# Schematic.net
KiCad netlist of a schematic drawn in EAGLE
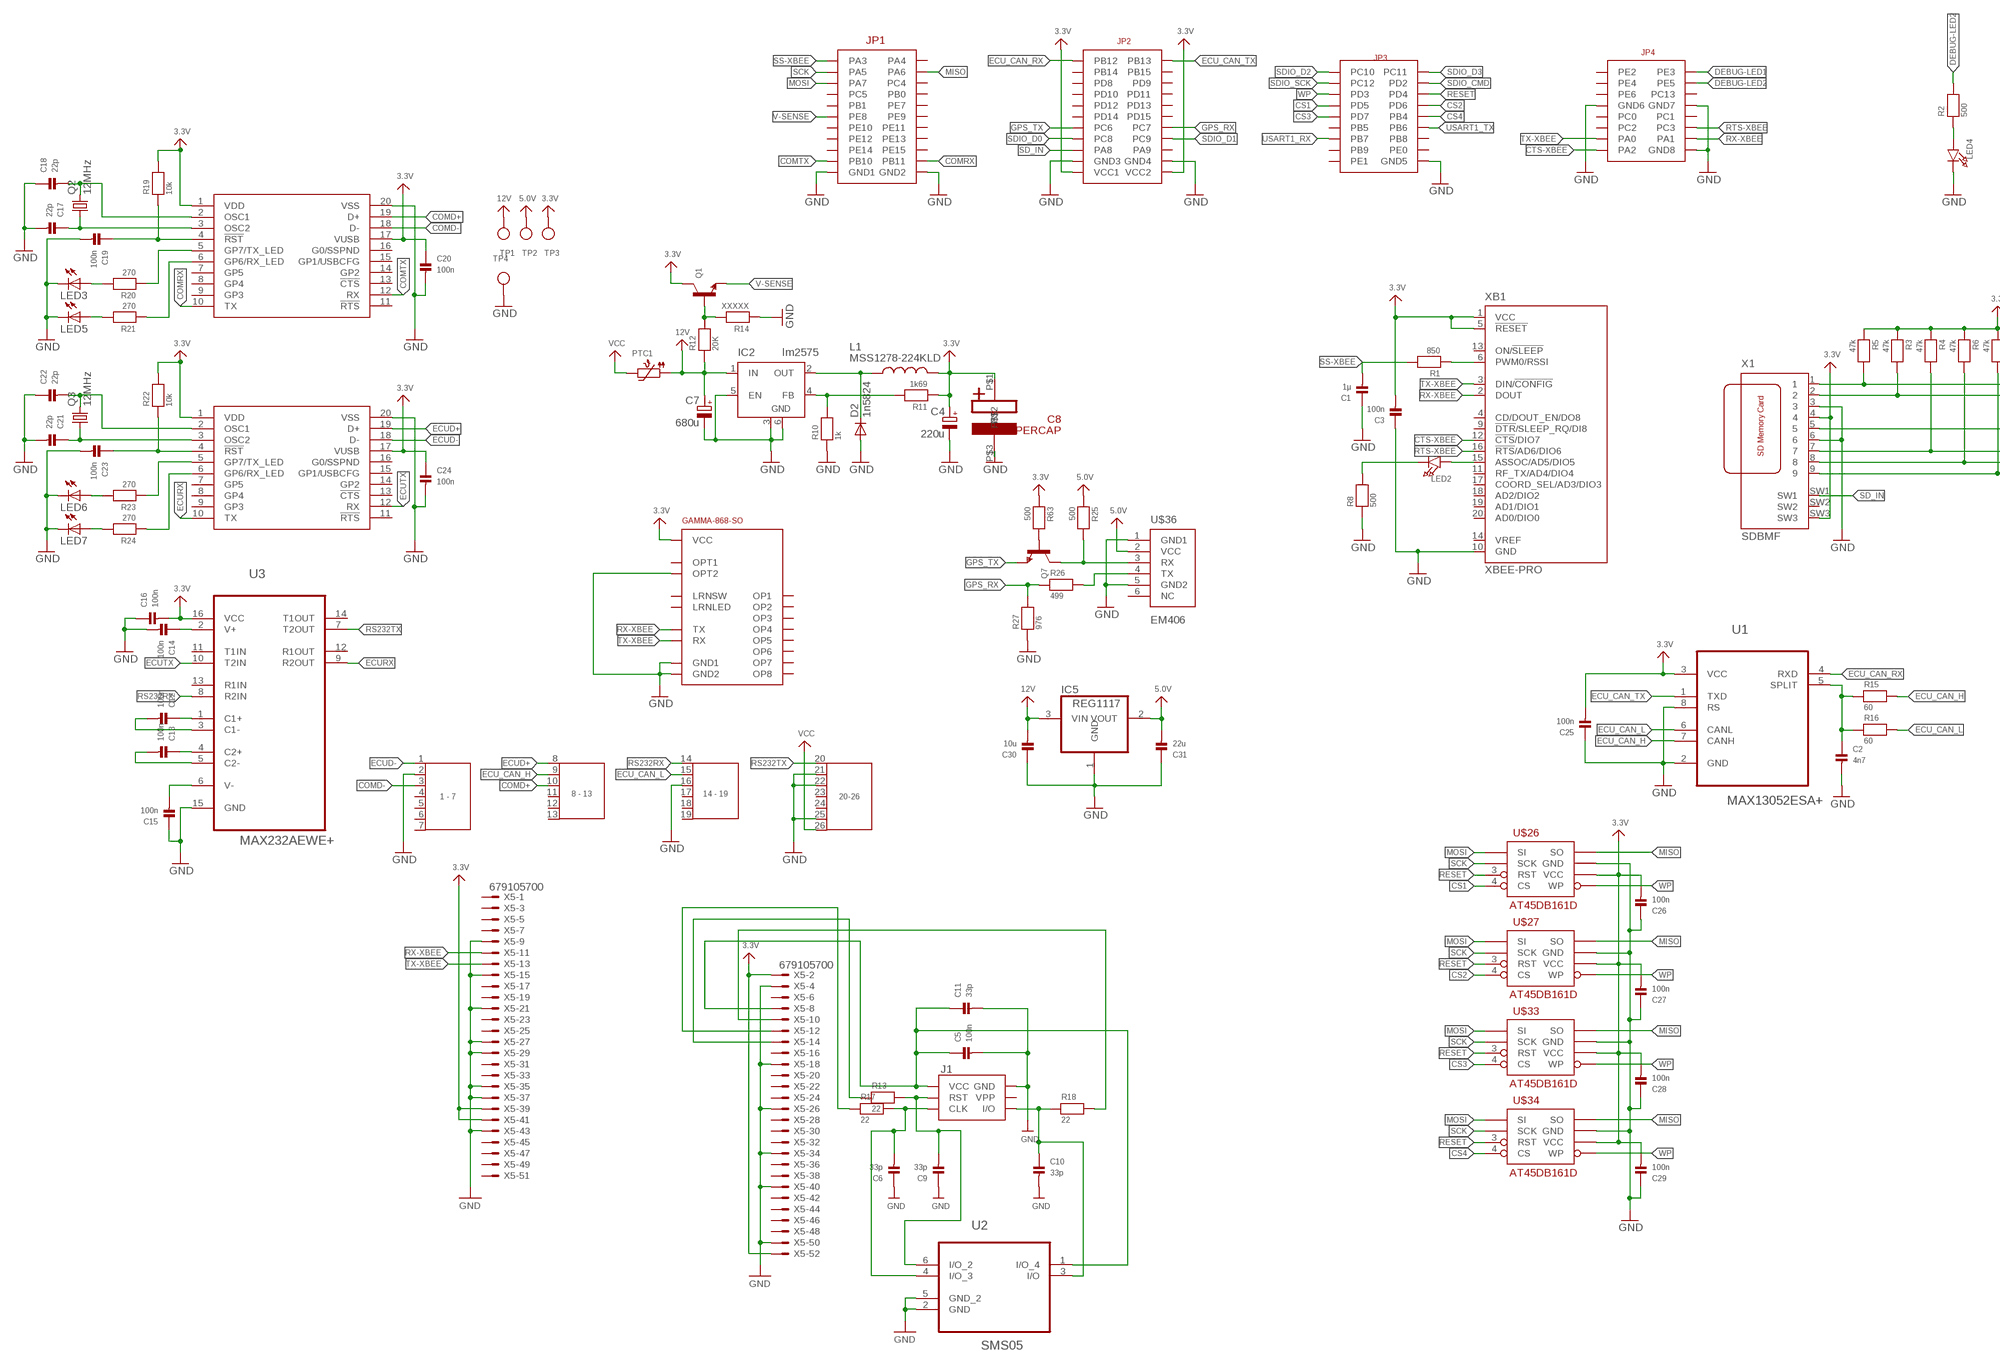
[diagram p0: schematic, sheet 1, part 1 of 2]
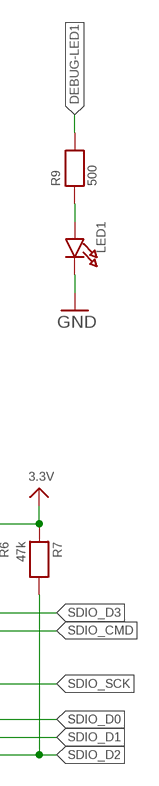
[diagram p1: schematic, sheet 1, part 2 of 2]

(export (version "E")
  (design (tool "Eeschema 10.0.6"))
  (components
    (comp (ref "C1")
      (value "1µ")
      (footprint "eagle-import:_0805")
      (libsource (lib "eagle-import") (part "CAP_CERAMIC_0805"))
    )
    (comp (ref "C2")
      (value "4n7")
      (footprint "eagle-import:0603")
      (libsource (lib "eagle-import") (part "CAP_CERAMIC0603"))
    )
    (comp (ref "C3")
      (value "100n")
      (footprint "eagle-import:_0603")
      (libsource (lib "eagle-import") (part "CAP_CERAMIC_0603"))
    )
    (comp (ref "C4")
      (value "220u")
      (footprint "eagle-import:E3,5-8")
      (libsource (lib "eagle-import") (part "CPOL-EUE3.5-8"))
    )
    (comp (ref "C5")
      (value "100n")
      (footprint "eagle-import:_0603")
      (libsource (lib "eagle-import") (part "CAP_CERAMIC_0603"))
    )
    (comp (ref "C6")
      (value "33p")
      (footprint "eagle-import:_0603")
      (libsource (lib "eagle-import") (part "CAP_CERAMIC_0603"))
    )
    (comp (ref "C7")
      (value "680u")
      (footprint "eagle-import:E5-10,5")
      (libsource (lib "eagle-import") (part "CPOL-EUE5-10.5"))
    )
    (comp (ref "C8")
      (value "SUPERCAP")
      (footprint "eagle-import:SUPERCAP")
      (libsource (lib "eagle-import") (part "SUPERCAP"))
    )
    (comp (ref "C9")
      (value "33p")
      (footprint "eagle-import:_0603")
      (libsource (lib "eagle-import") (part "CAP_CERAMIC_0603"))
    )
    (comp (ref "C10")
      (value "33p")
      (footprint "eagle-import:_0603")
      (libsource (lib "eagle-import") (part "CAP_CERAMIC_0603"))
    )
    (comp (ref "C11")
      (value "33p")
      (footprint "eagle-import:_0603")
      (libsource (lib "eagle-import") (part "CAP_CERAMIC_0603"))
    )
    (comp (ref "C12")
      (value "100n")
      (footprint "eagle-import:_0603")
      (libsource (lib "eagle-import") (part "CAP_CERAMIC_0603"))
    )
    (comp (ref "C13")
      (value "100n")
      (footprint "eagle-import:_0603")
      (libsource (lib "eagle-import") (part "CAP_CERAMIC_0603"))
    )
    (comp (ref "C14")
      (value "100n")
      (footprint "eagle-import:_0603")
      (libsource (lib "eagle-import") (part "CAP_CERAMIC_0603"))
    )
    (comp (ref "C15")
      (value "100n")
      (footprint "eagle-import:_0603")
      (libsource (lib "eagle-import") (part "CAP_CERAMIC_0603"))
    )
    (comp (ref "C16")
      (value "100n")
      (footprint "eagle-import:_0603")
      (libsource (lib "eagle-import") (part "CAP_CERAMIC_0603"))
    )
    (comp (ref "C17")
      (value "22p")
      (footprint "eagle-import:_0603")
      (libsource (lib "eagle-import") (part "CAP_CERAMIC_0603"))
    )
    (comp (ref "C18")
      (value "22p")
      (footprint "eagle-import:_0603")
      (libsource (lib "eagle-import") (part "CAP_CERAMIC_0603"))
    )
    (comp (ref "C19")
      (value "100n")
      (footprint "eagle-import:_0603")
      (libsource (lib "eagle-import") (part "CAP_CERAMIC_0603"))
    )
    (comp (ref "C20")
      (value "100n")
      (footprint "eagle-import:_0603")
      (libsource (lib "eagle-import") (part "CAP_CERAMIC_0603"))
    )
    (comp (ref "C21")
      (value "22p")
      (footprint "eagle-import:_0603")
      (libsource (lib "eagle-import") (part "CAP_CERAMIC_0603"))
    )
    (comp (ref "C22")
      (value "22p")
      (footprint "eagle-import:_0603")
      (libsource (lib "eagle-import") (part "CAP_CERAMIC_0603"))
    )
    (comp (ref "C23")
      (value "100n")
      (footprint "eagle-import:_0603")
      (libsource (lib "eagle-import") (part "CAP_CERAMIC_0603"))
    )
    (comp (ref "C24")
      (value "100n")
      (footprint "eagle-import:_0603")
      (libsource (lib "eagle-import") (part "CAP_CERAMIC_0603"))
    )
    (comp (ref "C25")
      (value "100n")
      (footprint "eagle-import:_0603")
      (libsource (lib "eagle-import") (part "CAP_CERAMIC_0603"))
    )
    (comp (ref "C26")
      (value "100n")
      (footprint "eagle-import:_0603")
      (libsource (lib "eagle-import") (part "CAP_CERAMIC_0603"))
    )
    (comp (ref "C27")
      (value "100n")
      (footprint "eagle-import:_0603")
      (libsource (lib "eagle-import") (part "CAP_CERAMIC_0603"))
    )
    (comp (ref "C28")
      (value "100n")
      (footprint "eagle-import:_0603")
      (libsource (lib "eagle-import") (part "CAP_CERAMIC_0603"))
    )
    (comp (ref "C29")
      (value "100n")
      (footprint "eagle-import:_0603")
      (libsource (lib "eagle-import") (part "CAP_CERAMIC_0603"))
    )
    (comp (ref "C30")
      (value "10u")
      (footprint "eagle-import:_0805")
      (libsource (lib "eagle-import") (part "CAP_CERAMIC_0805"))
    )
    (comp (ref "C31")
      (value "22u")
      (footprint "eagle-import:_0805")
      (libsource (lib "eagle-import") (part "CAP_CERAMIC_0805"))
    )
    (comp (ref "D2")
      (value "1n5824")
      (footprint "eagle-import:DO201-15")
      (libsource (lib "eagle-import") (part "1N5400"))
    )
    (comp (ref "IC2")
      (value "lm2575")
      (footprint "eagle-import:TO263-5")
      (libsource (lib "eagle-import") (part "LM2596S"))
    )
    (comp (ref "IC5")
      (value "REG1117")
      (footprint "eagle-import:SOT223")
      (libsource (lib "eagle-import") (part "REG1117"))
    )
    (comp (ref "J1")
      (value "SIMHOLDERSIM")
      (footprint "eagle-import:SIMHOLDER")
      (libsource (lib "eagle-import") (part "SIMHOLDERSIM"))
    )
    (comp (ref "L1")
      (value "MSS1278-224KLD")
      (footprint "eagle-import:CDRH125")
      (libsource (lib "eagle-import") (part "INDUCTORPWR"))
    )
    (comp (ref "LED1")
      (value "LED1206")
      (footprint "eagle-import:CHIPLED_1206")
      (libsource (lib "eagle-import") (part "LED1206"))
    )
    (comp (ref "LED2")
      (value "LED1206")
      (footprint "eagle-import:CHIPLED_1206")
      (libsource (lib "eagle-import") (part "LED1206"))
    )
    (comp (ref "LED3")
      (value "LEDCHIPLED_0805")
      (footprint "eagle-import:CHIPLED_0805")
      (libsource (lib "eagle-import") (part "LEDCHIPLED_0805"))
    )
    (comp (ref "LED4")
      (value "LED1206")
      (footprint "eagle-import:CHIPLED_1206")
      (libsource (lib "eagle-import") (part "LED1206"))
    )
    (comp (ref "LED5")
      (value "LEDCHIPLED_0805")
      (footprint "eagle-import:CHIPLED_0805")
      (libsource (lib "eagle-import") (part "LEDCHIPLED_0805"))
    )
    (comp (ref "LED6")
      (value "LEDCHIPLED_0805")
      (footprint "eagle-import:CHIPLED_0805")
      (libsource (lib "eagle-import") (part "LEDCHIPLED_0805"))
    )
    (comp (ref "LED7")
      (value "LEDCHIPLED_0805")
      (footprint "eagle-import:CHIPLED_0805")
      (libsource (lib "eagle-import") (part "LEDCHIPLED_0805"))
    )
    (comp (ref "PTC1")
      (value "PTC1812")
      (footprint "eagle-import:PTC1812")
      (libsource (lib "eagle-import") (part "PTC1812"))
    )
    (comp (ref "Q1")
      (value "TRANSISTOR_NPNWIDE")
      (footprint "eagle-import:SOT23-WIDE")
      (libsource (lib "eagle-import") (part "TRANSISTOR_NPNWIDE"))
    )
    (comp (ref "Q2")
      (value "12MHz")
      (footprint "eagle-import:HC49_S")
      (libsource (lib "eagle-import") (part "CRYSTALHC49S"))
    )
    (comp (ref "Q3")
      (value "12MHz")
      (footprint "eagle-import:HC49_S")
      (libsource (lib "eagle-import") (part "CRYSTALHC49S"))
    )
    (comp (ref "Q7")
      (value "TRANSISTOR_NPNWIDE")
      (footprint "eagle-import:SOT23-WIDE")
      (libsource (lib "eagle-import") (part "TRANSISTOR_NPNWIDE"))
    )
    (comp (ref "R1")
      (value "850")
      (footprint "eagle-import:_0603")
      (libsource (lib "eagle-import") (part "RESISTOR_0603"))
    )
    (comp (ref "R2")
      (value "500")
      (footprint "eagle-import:_0603")
      (libsource (lib "eagle-import") (part "RESISTOR_0603"))
    )
    (comp (ref "R3")
      (value "47k")
      (footprint "eagle-import:_0603")
      (libsource (lib "eagle-import") (part "RESISTOR_0603"))
    )
    (comp (ref "R4")
      (value "47k")
      (footprint "eagle-import:_0603")
      (libsource (lib "eagle-import") (part "RESISTOR_0603"))
    )
    (comp (ref "R5")
      (value "47k")
      (footprint "eagle-import:_0603")
      (libsource (lib "eagle-import") (part "RESISTOR_0603"))
    )
    (comp (ref "R6")
      (value "47k")
      (footprint "eagle-import:_0603")
      (libsource (lib "eagle-import") (part "RESISTOR_0603"))
    )
    (comp (ref "R7")
      (value "47k")
      (footprint "eagle-import:_0603")
      (libsource (lib "eagle-import") (part "RESISTOR_0603"))
    )
    (comp (ref "R8")
      (value "500")
      (footprint "eagle-import:_0603")
      (libsource (lib "eagle-import") (part "RESISTOR_0603"))
    )
    (comp (ref "R9")
      (value "500")
      (footprint "eagle-import:_0603")
      (libsource (lib "eagle-import") (part "RESISTOR_0603"))
    )
    (comp (ref "R10")
      (value "1k")
      (footprint "eagle-import:_0603")
      (libsource (lib "eagle-import") (part "RESISTOR_0603"))
    )
    (comp (ref "R11")
      (value "1k69")
      (footprint "eagle-import:_0603")
      (libsource (lib "eagle-import") (part "RESISTOR_0603"))
    )
    (comp (ref "R12")
      (value "20K")
      (footprint "eagle-import:_0603")
      (libsource (lib "eagle-import") (part "RESISTOR_0603"))
    )
    (comp (ref "R13")
      (value "22")
      (footprint "eagle-import:_0603")
      (libsource (lib "eagle-import") (part "RESISTOR_0603"))
    )
    (comp (ref "R14")
      (value "XXXXX")
      (footprint "eagle-import:_0603")
      (libsource (lib "eagle-import") (part "RESISTOR_0603"))
    )
    (comp (ref "R15")
      (value "60")
      (footprint "eagle-import:_0603")
      (libsource (lib "eagle-import") (part "RESISTOR_0603"))
    )
    (comp (ref "R16")
      (value "60")
      (footprint "eagle-import:_0603")
      (libsource (lib "eagle-import") (part "RESISTOR_0603"))
    )
    (comp (ref "R17")
      (value "22")
      (footprint "eagle-import:_0603")
      (libsource (lib "eagle-import") (part "RESISTOR_0603"))
    )
    (comp (ref "R18")
      (value "22")
      (footprint "eagle-import:_0603")
      (libsource (lib "eagle-import") (part "RESISTOR_0603"))
    )
    (comp (ref "R19")
      (value "10k")
      (footprint "eagle-import:_0603")
      (libsource (lib "eagle-import") (part "RESISTOR_0603"))
    )
    (comp (ref "R20")
      (value "270")
      (footprint "eagle-import:_0603")
      (libsource (lib "eagle-import") (part "RESISTOR_0603"))
    )
    (comp (ref "R21")
      (value "270")
      (footprint "eagle-import:_0603")
      (libsource (lib "eagle-import") (part "RESISTOR_0603"))
    )
    (comp (ref "R22")
      (value "10k")
      (footprint "eagle-import:_0603")
      (libsource (lib "eagle-import") (part "RESISTOR_0603"))
    )
    (comp (ref "R23")
      (value "270")
      (footprint "eagle-import:_0603")
      (libsource (lib "eagle-import") (part "RESISTOR_0603"))
    )
    (comp (ref "R24")
      (value "270")
      (footprint "eagle-import:_0603")
      (libsource (lib "eagle-import") (part "RESISTOR_0603"))
    )
    (comp (ref "R25")
      (value "500")
      (footprint "eagle-import:_0603")
      (libsource (lib "eagle-import") (part "RESISTOR_0603"))
    )
    (comp (ref "R26")
      (value "499")
      (footprint "eagle-import:_0603")
      (libsource (lib "eagle-import") (part "RESISTOR_0603"))
    )
    (comp (ref "R27")
      (value "976")
      (footprint "eagle-import:_0603")
      (libsource (lib "eagle-import") (part "RESISTOR_0603"))
    )
    (comp (ref "R63")
      (value "500")
      (footprint "eagle-import:_0603")
      (libsource (lib "eagle-import") (part "RESISTOR_0603"))
    )
    (comp (ref "TP1")
      (value "TESTPOINT")
      (footprint "eagle-import:TESTPOINT_SMT")
      (libsource (lib "eagle-import") (part "TESTPOINT"))
    )
    (comp (ref "TP2")
      (value "TESTPOINT")
      (footprint "eagle-import:TESTPOINT_SMT")
      (libsource (lib "eagle-import") (part "TESTPOINT"))
    )
    (comp (ref "TP3")
      (value "TESTPOINT")
      (footprint "eagle-import:TESTPOINT_SMT")
      (libsource (lib "eagle-import") (part "TESTPOINT"))
    )
    (comp (ref "TP4")
      (value "TESTPOINT")
      (footprint "eagle-import:TESTPOINT_SMT")
      (libsource (lib "eagle-import") (part "TESTPOINT"))
    )
    (comp (ref "U$1")
      (value "CPU-BOARD")
      (footprint "eagle-import:CPU-BOARD-JP1")
      (libsource (lib "eagle-import") (part "CPU-BOARD"))
    )
    (comp (ref "U$18")
      (value "SUPERSEAL-26")
      (footprint "eagle-import:SUPERSEAL-26")
      (libsource (lib "eagle-import") (part "SUPERSEAL-26"))
    )
    (comp (ref "U$24")
      (value "MCP2200")
      (footprint "eagle-import:SO20L")
      (libsource (lib "eagle-import") (part "MCP2200"))
    )
    (comp (ref "U$26")
      (value "AT45DB161D")
      (footprint "eagle-import:SO08-EIAJ")
      (libsource (lib "eagle-import") (part "AT45DB161D"))
    )
    (comp (ref "U$27")
      (value "AT45DB161D")
      (footprint "eagle-import:SO08-EIAJ")
      (libsource (lib "eagle-import") (part "AT45DB161D"))
    )
    (comp (ref "U$29")
      (value "MCP2200")
      (footprint "eagle-import:SO20L")
      (libsource (lib "eagle-import") (part "MCP2200"))
    )
    (comp (ref "U$32")
      (value "GAMMA-868-SO")
      (footprint "eagle-import:UNICORN_V2_GAMMA-868-SO")
      (libsource (lib "eagle-import") (part "GAMMA-868-SO"))
    )
    (comp (ref "U$33")
      (value "AT45DB161D")
      (footprint "eagle-import:SO08-EIAJ")
      (libsource (lib "eagle-import") (part "AT45DB161D"))
    )
    (comp (ref "U$34")
      (value "AT45DB161D")
      (footprint "eagle-import:SO08-EIAJ")
      (libsource (lib "eagle-import") (part "AT45DB161D"))
    )
    (comp (ref "U$36")
      (value "EM406")
      (footprint "eagle-import:EM406")
      (libsource (lib "eagle-import") (part "EM406"))
    )
    (comp (ref "U1")
      (value "MAX13052ESA+")
      (footprint "eagle-import:SOIC127P600X175-8N")
      (fields
        (field (name "MPN") "MAX13052ESA+")
        (field (name "OC_FARNELL") "1600112")
        (field (name "OC_NEWARK") "99K2875")
        (field (name "PACKAGE") "SOIC-8")
        (field (name "SUPPLIER") "Maxim")
      )
      (libsource (lib "eagle-import") (part "MAX13052ESA+"))
    )
    (comp (ref "U2")
      (value "SMS05")
      (footprint "eagle-import:SOT95P280X145-6N")
      (libsource (lib "eagle-import") (part "SMS05"))
    )
    (comp (ref "U3")
      (value "MAX232AEWE+")
      (footprint "eagle-import:SOIC127P1032X265-16N")
      (libsource (lib "eagle-import") (part "MAX232AEWE+"))
    )
    (comp (ref "X1")
      (value "SDBMF")
      (footprint "eagle-import:SDBMF-009XXBXX2")
      (libsource (lib "eagle-import") (part "SDBMF"))
    )
    (comp (ref "X5")
      (value "679105700")
      (footprint "eagle-import:679105700")
      (fields (field (name "MPN") "67910-5700"))
      (libsource (lib "eagle-import") (part "679105700"))
    )
    (comp (ref "XB1")
      (value "XBEE-PRO")
      (footprint "eagle-import:XBEE-PRO")
      (fields (field (name "MPN") "XBP24-AWI-001"))
      (libsource (lib "eagle-import") (part "XBEE-PRO"))
    )
  )
  (nets
    (net (code "1") (name "3.3V") (class "Default")
      (node (ref "C16") (pin "2") (pinfunction "P$2_2") (pintype "passive"))
      (node (ref "C20") (pin "1") (pinfunction "P$1_1") (pintype "passive"))
      (node (ref "C24") (pin "1") (pinfunction "P$1_1") (pintype "passive"))
      (node (ref "C25") (pin "2") (pinfunction "P$2_2") (pintype "passive"))
      (node (ref "C26") (pin "2") (pinfunction "P$2_2") (pintype "passive"))
      (node (ref "C27") (pin "2") (pinfunction "P$2_2") (pintype "passive"))
      (node (ref "C28") (pin "2") (pinfunction "P$2_2") (pintype "passive"))
      (node (ref "C29") (pin "2") (pinfunction "P$2_2") (pintype "passive"))
      (node (ref "C3") (pin "2") (pinfunction "P$2_2") (pintype "passive"))
      (node (ref "C4") (pin "+") (pinfunction "+_+") (pintype "passive"))
      (node (ref "C8") (pin "P$1") (pinfunction "P$1_P$1") (pintype "bidirectional"))
      (node (ref "L1") (pin "2") (pinfunction "2_2") (pintype "passive"))
      (node (ref "Q1") (pin "3") (pinfunction "C_3") (pintype "passive"))
      (node (ref "R11") (pin "1") (pinfunction "1_1") (pintype "passive"))
      (node (ref "R19") (pin "2") (pinfunction "2_2") (pintype "passive"))
      (node (ref "R22") (pin "2") (pinfunction "2_2") (pintype "passive"))
      (node (ref "R3") (pin "1") (pinfunction "1_1") (pintype "passive"))
      (node (ref "R4") (pin "1") (pinfunction "1_1") (pintype "passive"))
      (node (ref "R5") (pin "1") (pinfunction "1_1") (pintype "passive"))
      (node (ref "R6") (pin "1") (pinfunction "1_1") (pintype "passive"))
      (node (ref "R63") (pin "1") (pinfunction "1_1") (pintype "passive"))
      (node (ref "R7") (pin "1") (pinfunction "1_1") (pintype "passive"))
      (node (ref "TP3") (pin "P$1") (pinfunction "P$1_P$1") (pintype "bidirectional"))
      (node (ref "U$1") (pin "P$43") (pinfunction "VCC1_P$43") (pintype "bidirectional"))
      (node (ref "U$1") (pin "P$44") (pinfunction "VCC2_P$44") (pintype "bidirectional"))
      (node (ref "U$24") (pin "1") (pinfunction "VDD_1") (pintype "bidirectional"))
      (node (ref "U$24") (pin "17") (pinfunction "VUSB_17") (pintype "bidirectional"))
      (node (ref "U$26") (pin "6") (pinfunction "VCC_6") (pintype "bidirectional"))
      (node (ref "U$27") (pin "6") (pinfunction "VCC_6") (pintype "bidirectional"))
      (node (ref "U$29") (pin "1") (pinfunction "VDD_1") (pintype "bidirectional"))
      (node (ref "U$29") (pin "17") (pinfunction "VUSB_17") (pintype "bidirectional"))
      (node (ref "U$32") (pin "P$16") (pinfunction "VCC_P$16") (pintype "bidirectional"))
      (node (ref "U$33") (pin "6") (pinfunction "VCC_6") (pintype "bidirectional"))
      (node (ref "U$34") (pin "6") (pinfunction "VCC_6") (pintype "bidirectional"))
      (node (ref "U1") (pin "3") (pinfunction "VCC_3") (pintype "power_in"))
      (node (ref "U3") (pin "16") (pinfunction "VCC_16") (pintype "power_in"))
      (node (ref "X1") (pin "4") (pinfunction "4_4") (pintype "passive"))
      (node (ref "X1") (pin "SW3") (pinfunction "SW3_SW3") (pintype "passive"))
      (node (ref "X5") (pin "2") (pinfunction "S_2") (pintype "passive"))
      (node (ref "X5") (pin "39") (pinfunction "S_39") (pintype "passive"))
      (node (ref "X5") (pin "41") (pinfunction "S_41") (pintype "passive"))
      (node (ref "X5") (pin "52") (pinfunction "S_52") (pintype "passive"))
      (node (ref "XB1") (pin "1") (pinfunction "VCC_1") (pintype "power_in"))
      (node (ref "XB1") (pin "5") (pinfunction "~{RESET}_5") (pintype "input"))
    )
    (net (code "2") (name "5.0V") (class "Default")
      (node (ref "C31") (pin "2") (pinfunction "P$2_2") (pintype "passive"))
      (node (ref "IC5") (pin "2") (pinfunction "VOUT_2") (pintype "output"))
      (node (ref "R25") (pin "1") (pinfunction "1_1") (pintype "passive"))
      (node (ref "TP2") (pin "P$1") (pinfunction "P$1_P$1") (pintype "bidirectional"))
      (node (ref "U$36") (pin "2") (pinfunction "VCC_2") (pintype "bidirectional"))
    )
    (net (code "3") (name "12V") (class "Default")
      (node (ref "C30") (pin "2") (pinfunction "P$2_2") (pintype "passive"))
      (node (ref "C7") (pin "+") (pinfunction "+_+") (pintype "passive"))
      (node (ref "IC2") (pin "1") (pinfunction "IN_1") (pintype "input"))
      (node (ref "IC5") (pin "3") (pinfunction "VIN_3") (pintype "input"))
      (node (ref "PTC1") (pin "P$1") (pinfunction "1_P$1") (pintype "passive"))
      (node (ref "R12") (pin "1") (pinfunction "1_1") (pintype "passive"))
      (node (ref "TP1") (pin "P$1") (pinfunction "P$1_P$1") (pintype "bidirectional"))
    )
    (net (code "4") (name "COMD+") (class "Default")
      (node (ref "U$18") (pin "10") (pinfunction "P$3_10") (pintype "bidirectional"))
      (node (ref "U$24") (pin "19") (pinfunction "D+_19") (pintype "bidirectional"))
    )
    (net (code "5") (name "COMD-") (class "Default")
      (node (ref "U$18") (pin "3") (pinfunction "P$3_3") (pintype "bidirectional"))
      (node (ref "U$24") (pin "18") (pinfunction "D-_18") (pintype "bidirectional"))
    )
    (net (code "6") (name "COMRX") (class "Default")
      (node (ref "U$1") (pin "P$22") (pinfunction "PB11_P$22") (pintype "bidirectional"))
      (node (ref "U$24") (pin "10") (pinfunction "TX_10") (pintype "bidirectional"))
    )
    (net (code "7") (name "COMTX") (class "Default")
      (node (ref "U$1") (pin "P$21") (pinfunction "PB10_P$21") (pintype "bidirectional"))
      (node (ref "U$24") (pin "12") (pinfunction "RX_12") (pintype "bidirectional"))
    )
    (net (code "8") (name "CS1") (class "Default")
      (node (ref "U$1") (pin "P$51") (pinfunction "PD5_P$51") (pintype "bidirectional"))
      (node (ref "U$26") (pin "4") (pinfunction "CS_4") (pintype "bidirectional"))
    )
    (net (code "9") (name "CS2") (class "Default")
      (node (ref "U$1") (pin "P$52") (pinfunction "PD6_P$52") (pintype "bidirectional"))
      (node (ref "U$27") (pin "4") (pinfunction "CS_4") (pintype "bidirectional"))
    )
    (net (code "10") (name "CS3") (class "Default")
      (node (ref "U$1") (pin "P$53") (pinfunction "PD7_P$53") (pintype "bidirectional"))
      (node (ref "U$33") (pin "4") (pinfunction "CS_4") (pintype "bidirectional"))
    )
    (net (code "11") (name "CS4") (class "Default")
      (node (ref "U$1") (pin "P$54") (pinfunction "PB4_P$54") (pintype "bidirectional"))
      (node (ref "U$34") (pin "4") (pinfunction "CS_4") (pintype "bidirectional"))
    )
    (net (code "12") (name "CTS-XBEE") (class "Default")
      (node (ref "U$1") (pin "P$77") (pinfunction "PA2_P$77") (pintype "bidirectional"))
      (node (ref "XB1") (pin "12") (pinfunction "~{CTS}/DIO7_12") (pintype "bidirectional"))
    )
    (net (code "13") (name "DEBUG-LED1") (class "Default")
      (node (ref "R9") (pin "2") (pinfunction "2_2") (pintype "passive"))
      (node (ref "U$1") (pin "P$64") (pinfunction "PE3_P$64") (pintype "bidirectional"))
    )
    (net (code "14") (name "DEBUG-LED2") (class "Default")
      (node (ref "R2") (pin "2") (pinfunction "2_2") (pintype "passive"))
      (node (ref "U$1") (pin "P$66") (pinfunction "PE5_P$66") (pintype "bidirectional"))
    )
    (net (code "15") (name "ECUD+") (class "Default")
      (node (ref "U$18") (pin "8") (pinfunction "P$1_8") (pintype "bidirectional"))
      (node (ref "U$29") (pin "19") (pinfunction "D+_19") (pintype "bidirectional"))
    )
    (net (code "16") (name "ECUD-") (class "Default")
      (node (ref "U$18") (pin "1") (pinfunction "P$1_1") (pintype "bidirectional"))
      (node (ref "U$29") (pin "18") (pinfunction "D-_18") (pintype "bidirectional"))
    )
    (net (code "17") (name "ECURX") (class "Default")
      (node (ref "U$29") (pin "10") (pinfunction "TX_10") (pintype "bidirectional"))
      (node (ref "U3") (pin "9") (pinfunction "R2OUT_9") (pintype "output"))
    )
    (net (code "18") (name "ECUTX") (class "Default")
      (node (ref "U$29") (pin "12") (pinfunction "RX_12") (pintype "bidirectional"))
      (node (ref "U3") (pin "10") (pinfunction "T2IN_10") (pintype "input"))
    )
    (net (code "19") (name "ECU_CAN_H") (class "Default")
      (node (ref "R15") (pin "2") (pinfunction "2_2") (pintype "passive"))
      (node (ref "U$18") (pin "9") (pinfunction "P$2_9") (pintype "bidirectional"))
      (node (ref "U1") (pin "7") (pinfunction "CANH_7") (pintype "input"))
    )
    (net (code "20") (name "ECU_CAN_L") (class "Default")
      (node (ref "R16") (pin "2") (pinfunction "2_2") (pintype "passive"))
      (node (ref "U$18") (pin "15") (pinfunction "P$2_15") (pintype "bidirectional"))
      (node (ref "U1") (pin "6") (pinfunction "CANL_6") (pintype "input"))
    )
    (net (code "21") (name "ECU_CAN_RX") (class "Default")
      (node (ref "U$1") (pin "P$23") (pinfunction "PB12_P$23") (pintype "bidirectional"))
      (node (ref "U1") (pin "4") (pinfunction "RXD_4") (pintype "output"))
    )
    (net (code "22") (name "ECU_CAN_TX") (class "Default")
      (node (ref "U$1") (pin "P$24") (pinfunction "PB13_P$24") (pintype "bidirectional"))
      (node (ref "U1") (pin "1") (pinfunction "TXD_1") (pintype "input"))
    )
    (net (code "23") (name "GND") (class "Default")
      (node (ref "C1") (pin "1") (pinfunction "P$1_1") (pintype "passive"))
      (node (ref "C10") (pin "2") (pinfunction "P$2_2") (pintype "passive"))
      (node (ref "C11") (pin "2") (pinfunction "P$2_2") (pintype "passive"))
      (node (ref "C14") (pin "2") (pinfunction "P$2_2") (pintype "passive"))
      (node (ref "C15") (pin "1") (pinfunction "P$1_1") (pintype "passive"))
      (node (ref "C16") (pin "1") (pinfunction "P$1_1") (pintype "passive"))
      (node (ref "C17") (pin "2") (pinfunction "P$2_2") (pintype "passive"))
      (node (ref "C18") (pin "1") (pinfunction "P$1_1") (pintype "passive"))
      (node (ref "C19") (pin "2") (pinfunction "P$2_2") (pintype "passive"))
      (node (ref "C2") (pin "2") (pinfunction "P$2_2") (pintype "passive"))
      (node (ref "C20") (pin "2") (pinfunction "P$2_2") (pintype "passive"))
      (node (ref "C21") (pin "2") (pinfunction "P$2_2") (pintype "passive"))
      (node (ref "C22") (pin "1") (pinfunction "P$1_1") (pintype "passive"))
      (node (ref "C23") (pin "2") (pinfunction "P$2_2") (pintype "passive"))
      (node (ref "C24") (pin "2") (pinfunction "P$2_2") (pintype "passive"))
      (node (ref "C25") (pin "1") (pinfunction "P$1_1") (pintype "passive"))
      (node (ref "C26") (pin "1") (pinfunction "P$1_1") (pintype "passive"))
      (node (ref "C27") (pin "1") (pinfunction "P$1_1") (pintype "passive"))
      (node (ref "C28") (pin "1") (pinfunction "P$1_1") (pintype "passive"))
      (node (ref "C29") (pin "1") (pinfunction "P$1_1") (pintype "passive"))
      (node (ref "C3") (pin "1") (pinfunction "P$1_1") (pintype "passive"))
      (node (ref "C30") (pin "1") (pinfunction "P$1_1") (pintype "passive"))
      (node (ref "C31") (pin "1") (pinfunction "P$1_1") (pintype "passive"))
      (node (ref "C4") (pin "-") (pinfunction "-_-") (pintype "passive"))
      (node (ref "C5") (pin "2") (pinfunction "P$2_2") (pintype "passive"))
      (node (ref "C6") (pin "1") (pinfunction "P$1_1") (pintype "passive"))
      (node (ref "C7") (pin "-") (pinfunction "-_-") (pintype "passive"))
      (node (ref "C8") (pin "P$3") (pinfunction "P$2_P$3") (pintype "bidirectional"))
      (node (ref "C9") (pin "1") (pinfunction "P$1_1") (pintype "passive"))
      (node (ref "D2") (pin "A") (pinfunction "A_A") (pintype "passive"))
      (node (ref "IC2") (pin "3") (pinfunction "GND_3") (pintype "power_in"))
      (node (ref "IC2") (pin "5") (pinfunction "EN_5") (pintype "input"))
      (node (ref "IC2") (pin "6") (pinfunction "GND_6") (pintype "power_in"))
      (node (ref "IC5") (pin "1") (pinfunction "GND_1") (pintype "power_in"))
      (node (ref "J1") (pin "C5") (pinfunction "GND_C5") (pintype "power_in"))
      (node (ref "LED1") (pin "C") (pinfunction "C_C") (pintype "passive"))
      (node (ref "LED3") (pin "C") (pinfunction "C_C") (pintype "passive"))
      (node (ref "LED4") (pin "C") (pinfunction "C_C") (pintype "passive"))
      (node (ref "LED5") (pin "C") (pinfunction "C_C") (pintype "passive"))
      (node (ref "LED6") (pin "C") (pinfunction "C_C") (pintype "passive"))
      (node (ref "LED7") (pin "C") (pinfunction "C_C") (pintype "passive"))
      (node (ref "R10") (pin "1") (pinfunction "1_1") (pintype "passive"))
      (node (ref "R14") (pin "1") (pinfunction "1_1") (pintype "passive"))
      (node (ref "R27") (pin "1") (pinfunction "1_1") (pintype "passive"))
      (node (ref "R8") (pin "1") (pinfunction "1_1") (pintype "passive"))
      (node (ref "TP4") (pin "P$1") (pinfunction "P$1_P$1") (pintype "bidirectional"))
      (node (ref "U$1") (pin "P$19") (pinfunction "GND1_P$19") (pintype "bidirectional"))
      (node (ref "U$1") (pin "P$20") (pinfunction "GND2_P$20") (pintype "bidirectional"))
      (node (ref "U$1") (pin "P$41") (pinfunction "GND3_P$41") (pintype "bidirectional"))
      (node (ref "U$1") (pin "P$42") (pinfunction "GND4_P$42") (pintype "bidirectional"))
      (node (ref "U$1") (pin "P$62") (pinfunction "GND5_P$62") (pintype "bidirectional"))
      (node (ref "U$1") (pin "P$69") (pinfunction "GND6_P$69") (pintype "bidirectional"))
      (node (ref "U$1") (pin "P$70") (pinfunction "GND7_P$70") (pintype "bidirectional"))
      (node (ref "U$1") (pin "P$78") (pinfunction "GND8_P$78") (pintype "bidirectional"))
      (node (ref "U$18") (pin "16") (pinfunction "P$3_16") (pintype "bidirectional"))
      (node (ref "U$18") (pin "2") (pinfunction "P$2_2") (pintype "bidirectional"))
      (node (ref "U$18") (pin "21") (pinfunction "P$2_21") (pintype "bidirectional"))
      (node (ref "U$18") (pin "22") (pinfunction "P$3_22") (pintype "bidirectional"))
      (node (ref "U$18") (pin "25") (pinfunction "P$6_25") (pintype "bidirectional"))
      (node (ref "U$24") (pin "20") (pinfunction "VSS_20") (pintype "bidirectional"))
      (node (ref "U$26") (pin "7") (pinfunction "GND_7") (pintype "bidirectional"))
      (node (ref "U$27") (pin "7") (pinfunction "GND_7") (pintype "bidirectional"))
      (node (ref "U$29") (pin "20") (pinfunction "VSS_20") (pintype "bidirectional"))
      (node (ref "U$32") (pin "P$14") (pinfunction "OPT2_P$14") (pintype "bidirectional"))
      (node (ref "U$32") (pin "P$15") (pinfunction "GND2_P$15") (pintype "bidirectional"))
      (node (ref "U$32") (pin "P$2") (pinfunction "GND1_P$2") (pintype "bidirectional"))
      (node (ref "U$33") (pin "7") (pinfunction "GND_7") (pintype "bidirectional"))
      (node (ref "U$34") (pin "7") (pinfunction "GND_7") (pintype "bidirectional"))
      (node (ref "U$36") (pin "1") (pinfunction "GND1_1") (pintype "bidirectional"))
      (node (ref "U$36") (pin "5") (pinfunction "GND2_5") (pintype "bidirectional"))
      (node (ref "U1") (pin "2") (pinfunction "GND_2") (pintype "passive"))
      (node (ref "U1") (pin "8") (pinfunction "RS_8") (pintype "input"))
      (node (ref "U2") (pin "2") (pinfunction "GND_2") (pintype "passive"))
      (node (ref "U2") (pin "5") (pinfunction "GND_2_5") (pintype "passive"))
      (node (ref "U3") (pin "15") (pinfunction "GND_15") (pintype "passive"))
      (node (ref "X1") (pin "3") (pinfunction "3_3") (pintype "passive"))
      (node (ref "X1") (pin "6") (pinfunction "6_6") (pintype "passive"))
      (node (ref "X5") (pin "15") (pinfunction "S_15") (pintype "passive"))
      (node (ref "X5") (pin "18") (pinfunction "S_18") (pintype "passive"))
      (node (ref "X5") (pin "21") (pinfunction "S_21") (pintype "passive"))
      (node (ref "X5") (pin "26") (pinfunction "S_26") (pintype "passive"))
      (node (ref "X5") (pin "27") (pinfunction "S_27") (pintype "passive"))
      (node (ref "X5") (pin "29") (pinfunction "S_29") (pintype "passive"))
      (node (ref "X5") (pin "34") (pinfunction "S_34") (pintype "passive"))
      (node (ref "X5") (pin "35") (pinfunction "S_35") (pintype "passive"))
      (node (ref "X5") (pin "37") (pinfunction "S_37") (pintype "passive"))
      (node (ref "X5") (pin "4") (pinfunction "S_4") (pintype "passive"))
      (node (ref "X5") (pin "40") (pinfunction "S_40") (pintype "passive"))
      (node (ref "X5") (pin "43") (pinfunction "S_43") (pintype "passive"))
      (node (ref "X5") (pin "50") (pinfunction "S_50") (pintype "passive"))
      (node (ref "X5") (pin "9") (pinfunction "S_9") (pintype "passive"))
      (node (ref "XB1") (pin "10") (pinfunction "GND_10") (pintype "power_in"))
    )
    (net (code "24") (name "GPS_RX") (class "Default")
      (node (ref "R26") (pin "1") (pinfunction "1_1") (pintype "passive"))
      (node (ref "R27") (pin "2") (pinfunction "2_2") (pintype "passive"))
      (node (ref "U$1") (pin "P$36") (pinfunction "PC7_P$36") (pintype "bidirectional"))
    )
    (net (code "25") (name "GPS_TX") (class "Default")
      (node (ref "Q7") (pin "2") (pinfunction "E_2") (pintype "passive"))
      (node (ref "U$1") (pin "P$35") (pinfunction "PC6_P$35") (pintype "bidirectional"))
    )
    (net (code "26") (name "MISO") (class "Default")
      (node (ref "U$1") (pin "P$4") (pinfunction "PA6_P$4") (pintype "bidirectional"))
      (node (ref "U$26") (pin "8") (pinfunction "SO_8") (pintype "bidirectional"))
      (node (ref "U$27") (pin "8") (pinfunction "SO_8") (pintype "bidirectional"))
      (node (ref "U$33") (pin "8") (pinfunction "SO_8") (pintype "bidirectional"))
      (node (ref "U$34") (pin "8") (pinfunction "SO_8") (pintype "bidirectional"))
    )
    (net (code "27") (name "MOSI") (class "Default")
      (node (ref "U$1") (pin "P$5") (pinfunction "PA7_P$5") (pintype "bidirectional"))
      (node (ref "U$26") (pin "1") (pinfunction "SI_1") (pintype "bidirectional"))
      (node (ref "U$27") (pin "1") (pinfunction "SI_1") (pintype "bidirectional"))
      (node (ref "U$33") (pin "1") (pinfunction "SI_1") (pintype "bidirectional"))
      (node (ref "U$34") (pin "1") (pinfunction "SI_1") (pintype "bidirectional"))
    )
    (net (code "28") (name "Net-(C2-P$1)") (class "Default")
      (node (ref "C2") (pin "1") (pinfunction "P$1_1") (pintype "passive"))
      (node (ref "R15") (pin "1") (pinfunction "1_1") (pintype "passive"))
      (node (ref "R16") (pin "1") (pinfunction "1_1") (pintype "passive"))
      (node (ref "U1") (pin "5") (pinfunction "SPLIT_5") (pintype "output"))
    )
    (net (code "29") (name "Net-(C6-P$2)") (class "Default")
      (node (ref "C6") (pin "2") (pinfunction "P$2_2") (pintype "passive"))
      (node (ref "J1") (pin "C3") (pinfunction "CLK_C3") (pintype "input"))
      (node (ref "R17") (pin "2") (pinfunction "2_2") (pintype "passive"))
      (node (ref "U2") (pin "4") (pinfunction "I/O_3_4") (pintype "bidirectional"))
    )
    (net (code "30") (name "Net-(C9-P$2)") (class "Default")
      (node (ref "C9") (pin "2") (pinfunction "P$2_2") (pintype "passive"))
      (node (ref "J1") (pin "C2") (pinfunction "RST_C2") (pintype "input"))
      (node (ref "R13") (pin "2") (pinfunction "2_2") (pintype "passive"))
      (node (ref "U2") (pin "6") (pinfunction "I/O_2_6") (pintype "bidirectional"))
    )
    (net (code "31") (name "Net-(C10-P$1)") (class "Default")
      (node (ref "C10") (pin "1") (pinfunction "P$1_1") (pintype "passive"))
      (node (ref "J1") (pin "C7") (pinfunction "I/O_C7") (pintype "bidirectional"))
      (node (ref "R18") (pin "1") (pinfunction "1_1") (pintype "passive"))
      (node (ref "U2") (pin "3") (pinfunction "I/O_3") (pintype "bidirectional"))
    )
    (net (code "32") (name "Net-(C11-P$1)") (class "Default")
      (node (ref "C11") (pin "1") (pinfunction "P$1_1") (pintype "passive"))
      (node (ref "C5") (pin "1") (pinfunction "P$1_1") (pintype "passive"))
      (node (ref "J1") (pin "C1") (pinfunction "VCC_C1") (pintype "power_in"))
      (node (ref "U2") (pin "1") (pinfunction "I/O_4_1") (pintype "bidirectional"))
      (node (ref "X5") (pin "8") (pinfunction "S_8") (pintype "passive"))
    )
    (net (code "33") (name "Net-(C12-P$1)") (class "Default")
      (node (ref "C12") (pin "1") (pinfunction "P$1_1") (pintype "passive"))
      (node (ref "U3") (pin "1") (pinfunction "C1+_1") (pintype "input"))
    )
    (net (code "34") (name "Net-(C12-P$2)") (class "Default")
      (node (ref "C12") (pin "2") (pinfunction "P$2_2") (pintype "passive"))
      (node (ref "U3") (pin "3") (pinfunction "C1-_3") (pintype "input"))
    )
    (net (code "35") (name "Net-(C13-P$1)") (class "Default")
      (node (ref "C13") (pin "1") (pinfunction "P$1_1") (pintype "passive"))
      (node (ref "U3") (pin "4") (pinfunction "C2+_4") (pintype "input"))
    )
    (net (code "36") (name "Net-(C13-P$2)") (class "Default")
      (node (ref "C13") (pin "2") (pinfunction "P$2_2") (pintype "passive"))
      (node (ref "U3") (pin "5") (pinfunction "C2-_5") (pintype "input"))
    )
    (net (code "37") (name "Net-(C14-P$1)") (class "Default")
      (node (ref "C14") (pin "1") (pinfunction "P$1_1") (pintype "passive"))
      (node (ref "U3") (pin "2") (pinfunction "V+_2") (pintype "power_in"))
    )
    (net (code "38") (name "Net-(C15-P$2)") (class "Default")
      (node (ref "C15") (pin "2") (pinfunction "P$2_2") (pintype "passive"))
      (node (ref "U3") (pin "6") (pinfunction "V-_6") (pintype "power_in"))
    )
    (net (code "39") (name "Net-(C17-P$1)") (class "Default")
      (node (ref "C17") (pin "1") (pinfunction "P$1_1") (pintype "passive"))
      (node (ref "Q2") (pin "1") (pinfunction "1_1") (pintype "passive"))
      (node (ref "U$24") (pin "3") (pinfunction "OSC2_3") (pintype "bidirectional"))
    )
    (net (code "40") (name "Net-(C18-P$2)") (class "Default")
      (node (ref "C18") (pin "2") (pinfunction "P$2_2") (pintype "passive"))
      (node (ref "Q2") (pin "2") (pinfunction "2_2") (pintype "passive"))
      (node (ref "U$24") (pin "2") (pinfunction "OSC1_2") (pintype "bidirectional"))
    )
    (net (code "41") (name "Net-(C19-P$1)") (class "Default")
      (node (ref "C19") (pin "1") (pinfunction "P$1_1") (pintype "passive"))
      (node (ref "R19") (pin "1") (pinfunction "1_1") (pintype "passive"))
      (node (ref "U$24") (pin "4") (pinfunction "~{RST}_4") (pintype "bidirectional"))
    )
    (net (code "42") (name "Net-(C21-P$1)") (class "Default")
      (node (ref "C21") (pin "1") (pinfunction "P$1_1") (pintype "passive"))
      (node (ref "Q3") (pin "1") (pinfunction "1_1") (pintype "passive"))
      (node (ref "U$29") (pin "3") (pinfunction "OSC2_3") (pintype "bidirectional"))
    )
    (net (code "43") (name "Net-(C22-P$2)") (class "Default")
      (node (ref "C22") (pin "2") (pinfunction "P$2_2") (pintype "passive"))
      (node (ref "Q3") (pin "2") (pinfunction "2_2") (pintype "passive"))
      (node (ref "U$29") (pin "2") (pinfunction "OSC1_2") (pintype "bidirectional"))
    )
    (net (code "44") (name "Net-(C23-P$1)") (class "Default")
      (node (ref "C23") (pin "1") (pinfunction "P$1_1") (pintype "passive"))
      (node (ref "R22") (pin "1") (pinfunction "1_1") (pintype "passive"))
      (node (ref "U$29") (pin "4") (pinfunction "~{RST}_4") (pintype "bidirectional"))
    )
    (net (code "45") (name "Net-(IC2-FB)") (class "Default")
      (node (ref "IC2") (pin "4") (pinfunction "FB_4") (pintype "input"))
      (node (ref "R10") (pin "2") (pinfunction "2_2") (pintype "passive"))
      (node (ref "R11") (pin "2") (pinfunction "2_2") (pintype "passive"))
    )
    (net (code "46") (name "Net-(IC2-OUT)") (class "Default")
      (node (ref "D2") (pin "C") (pinfunction "C_C") (pintype "passive"))
      (node (ref "IC2") (pin "2") (pinfunction "OUT_2") (pintype "output"))
      (node (ref "L1") (pin "1") (pinfunction "1_1") (pintype "passive"))
    )
    (net (code "47") (name "Net-(LED1-PadA)") (class "Default")
      (node (ref "LED1") (pin "A") (pinfunction "A_A") (pintype "passive"))
      (node (ref "R9") (pin "1") (pinfunction "1_1") (pintype "passive"))
    )
    (net (code "48") (name "Net-(LED2-PadC)") (class "Default")
      (node (ref "LED2") (pin "C") (pinfunction "C_C") (pintype "passive"))
      (node (ref "R8") (pin "2") (pinfunction "2_2") (pintype "passive"))
    )
    (net (code "49") (name "Net-(LED3-PadA)") (class "Default")
      (node (ref "LED3") (pin "A") (pinfunction "A_A") (pintype "passive"))
      (node (ref "R20") (pin "2") (pinfunction "2_2") (pintype "passive"))
    )
    (net (code "50") (name "Net-(LED4-PadA)") (class "Default")
      (node (ref "LED4") (pin "A") (pinfunction "A_A") (pintype "passive"))
      (node (ref "R2") (pin "1") (pinfunction "1_1") (pintype "passive"))
    )
    (net (code "51") (name "Net-(LED5-PadA)") (class "Default")
      (node (ref "LED5") (pin "A") (pinfunction "A_A") (pintype "passive"))
      (node (ref "R21") (pin "2") (pinfunction "2_2") (pintype "passive"))
    )
    (net (code "52") (name "Net-(LED6-PadA)") (class "Default")
      (node (ref "LED6") (pin "A") (pinfunction "A_A") (pintype "passive"))
      (node (ref "R23") (pin "2") (pinfunction "2_2") (pintype "passive"))
    )
    (net (code "53") (name "Net-(LED7-PadA)") (class "Default")
      (node (ref "LED7") (pin "A") (pinfunction "A_A") (pintype "passive"))
      (node (ref "R24") (pin "2") (pinfunction "2_2") (pintype "passive"))
    )
    (net (code "54") (name "Net-(Q1-B)") (class "Default")
      (node (ref "Q1") (pin "1") (pinfunction "B_1") (pintype "passive"))
      (node (ref "R12") (pin "2") (pinfunction "2_2") (pintype "passive"))
      (node (ref "R14") (pin "2") (pinfunction "2_2") (pintype "passive"))
    )
    (net (code "55") (name "Net-(Q7-B)") (class "Default")
      (node (ref "Q7") (pin "1") (pinfunction "B_1") (pintype "passive"))
      (node (ref "R63") (pin "2") (pinfunction "2_2") (pintype "passive"))
    )
    (net (code "56") (name "Net-(Q7-C)") (class "Default")
      (node (ref "Q7") (pin "3") (pinfunction "C_3") (pintype "passive"))
      (node (ref "R25") (pin "2") (pinfunction "2_2") (pintype "passive"))
      (node (ref "U$36") (pin "3") (pinfunction "RX_3") (pintype "bidirectional"))
    )
    (net (code "57") (name "Net-(U$24-GP6{slash}RX_LED)") (class "Default")
      (node (ref "R21") (pin "1") (pinfunction "1_1") (pintype "passive"))
      (node (ref "U$24") (pin "6") (pinfunction "GP6/RX_LED_6") (pintype "bidirectional"))
    )
    (net (code "58") (name "Net-(U$24-GP7{slash}TX_LED)") (class "Default")
      (node (ref "R20") (pin "1") (pinfunction "1_1") (pintype "passive"))
      (node (ref "U$24") (pin "5") (pinfunction "GP7/TX_LED_5") (pintype "bidirectional"))
    )
    (net (code "59") (name "Net-(U$29-GP6{slash}RX_LED)") (class "Default")
      (node (ref "R24") (pin "1") (pinfunction "1_1") (pintype "passive"))
      (node (ref "U$29") (pin "6") (pinfunction "GP6/RX_LED_6") (pintype "bidirectional"))
    )
    (net (code "60") (name "Net-(U$29-GP7{slash}TX_LED)") (class "Default")
      (node (ref "R23") (pin "1") (pinfunction "1_1") (pintype "passive"))
      (node (ref "U$29") (pin "5") (pinfunction "GP7/TX_LED_5") (pintype "bidirectional"))
    )
    (net (code "61") (name "Net-(U$36-TX)") (class "Default")
      (node (ref "R26") (pin "2") (pinfunction "2_2") (pintype "passive"))
      (node (ref "U$36") (pin "4") (pinfunction "TX_4") (pintype "bidirectional"))
    )
    (net (code "62") (name "Net-(X5B-S)") (class "Default")
      (node (ref "R18") (pin "2") (pinfunction "2_2") (pintype "passive"))
      (node (ref "X5") (pin "10") (pinfunction "S_10") (pintype "passive"))
    )
    (net (code "63") (name "Net-(X5D-S)") (class "Default")
      (node (ref "R17") (pin "1") (pinfunction "1_1") (pintype "passive"))
      (node (ref "X5") (pin "12") (pinfunction "S_12") (pintype "passive"))
    )
    (net (code "64") (name "Net-(X5F-S)") (class "Default")
      (node (ref "R13") (pin "1") (pinfunction "1_1") (pintype "passive"))
      (node (ref "X5") (pin "14") (pinfunction "S_14") (pintype "passive"))
    )
    (net (code "65") (name "Net-(XB1-ASSOC{slash}AD5{slash}DIO5)") (class "Default")
      (node (ref "LED2") (pin "A") (pinfunction "A_A") (pintype "passive"))
      (node (ref "XB1") (pin "15") (pinfunction "ASSOC/AD5/DIO5_15") (pintype "bidirectional"))
    )
    (net (code "66") (name "Net-(XB1-PWM0{slash}RSSI)") (class "Default")
      (node (ref "R1") (pin "1") (pinfunction "1_1") (pintype "passive"))
      (node (ref "XB1") (pin "6") (pinfunction "PWM0/RSSI_6") (pintype "output"))
    )
    (net (code "67") (name "RESET") (class "Default")
      (node (ref "U$1") (pin "P$50") (pinfunction "PD4_P$50") (pintype "bidirectional"))
      (node (ref "U$26") (pin "3") (pinfunction "RST_3") (pintype "bidirectional"))
      (node (ref "U$27") (pin "3") (pinfunction "RST_3") (pintype "bidirectional"))
      (node (ref "U$33") (pin "3") (pinfunction "RST_3") (pintype "bidirectional"))
      (node (ref "U$34") (pin "3") (pinfunction "RST_3") (pintype "bidirectional"))
    )
    (net (code "68") (name "RS232RX") (class "Default")
      (node (ref "U$18") (pin "14") (pinfunction "P$1_14") (pintype "bidirectional"))
      (node (ref "U3") (pin "8") (pinfunction "R2IN_8") (pintype "input"))
    )
    (net (code "69") (name "RS232TX") (class "Default")
      (node (ref "U$18") (pin "20") (pinfunction "P$1_20") (pintype "bidirectional"))
      (node (ref "U3") (pin "7") (pinfunction "T2OUT_7") (pintype "output"))
    )
    (net (code "70") (name "RTS-XBEE") (class "Default")
      (node (ref "U$1") (pin "P$74") (pinfunction "PC3_P$74") (pintype "bidirectional"))
      (node (ref "XB1") (pin "16") (pinfunction "~{RTS}/AD6/DIO6_16") (pintype "bidirectional"))
    )
    (net (code "71") (name "RX-XBEE") (class "Default")
      (node (ref "U$1") (pin "P$76") (pinfunction "PA1_P$76") (pintype "bidirectional"))
      (node (ref "U$32") (pin "P$17") (pinfunction "TX_P$17") (pintype "bidirectional"))
      (node (ref "X5") (pin "11") (pinfunction "S_11") (pintype "passive"))
      (node (ref "XB1") (pin "2") (pinfunction "DOUT_2") (pintype "output"))
    )
    (net (code "72") (name "SCK") (class "Default")
      (node (ref "U$1") (pin "P$3") (pinfunction "PA5_P$3") (pintype "bidirectional"))
      (node (ref "U$26") (pin "2") (pinfunction "SCK_2") (pintype "bidirectional"))
      (node (ref "U$27") (pin "2") (pinfunction "SCK_2") (pintype "bidirectional"))
      (node (ref "U$33") (pin "2") (pinfunction "SCK_2") (pintype "bidirectional"))
      (node (ref "U$34") (pin "2") (pinfunction "SCK_2") (pintype "bidirectional"))
    )
    (net (code "73") (name "SDIO_CMD") (class "Default")
      (node (ref "R3") (pin "2") (pinfunction "2_2") (pintype "passive"))
      (node (ref "U$1") (pin "P$48") (pinfunction "PD2_P$48") (pintype "bidirectional"))
      (node (ref "X1") (pin "2") (pinfunction "2_2") (pintype "passive"))
    )
    (net (code "74") (name "SDIO_D0") (class "Default")
      (node (ref "R4") (pin "2") (pinfunction "2_2") (pintype "passive"))
      (node (ref "U$1") (pin "P$37") (pinfunction "PC8_P$37") (pintype "bidirectional"))
      (node (ref "X1") (pin "7") (pinfunction "7_7") (pintype "passive"))
    )
    (net (code "75") (name "SDIO_D1") (class "Default")
      (node (ref "R6") (pin "2") (pinfunction "2_2") (pintype "passive"))
      (node (ref "U$1") (pin "P$38") (pinfunction "PC9_P$38") (pintype "bidirectional"))
      (node (ref "X1") (pin "8") (pinfunction "8_8") (pintype "passive"))
    )
    (net (code "76") (name "SDIO_D2") (class "Default")
      (node (ref "R7") (pin "2") (pinfunction "2_2") (pintype "passive"))
      (node (ref "U$1") (pin "P$45") (pinfunction "PC10_P$45") (pintype "bidirectional"))
      (node (ref "X1") (pin "9") (pinfunction "9_9") (pintype "passive"))
    )
    (net (code "77") (name "SDIO_D3") (class "Default")
      (node (ref "R5") (pin "2") (pinfunction "2_2") (pintype "passive"))
      (node (ref "U$1") (pin "P$46") (pinfunction "PC11_P$46") (pintype "bidirectional"))
      (node (ref "X1") (pin "1") (pinfunction "1_1") (pintype "passive"))
    )
    (net (code "78") (name "SDIO_SCK") (class "Default")
      (node (ref "U$1") (pin "P$47") (pinfunction "PC12_P$47") (pintype "bidirectional"))
      (node (ref "X1") (pin "5") (pinfunction "5_5") (pintype "passive"))
    )
    (net (code "79") (name "SD_IN") (class "Default")
      (node (ref "U$1") (pin "P$39") (pinfunction "PA8_P$39") (pintype "bidirectional"))
      (node (ref "X1") (pin "SW1") (pinfunction "SW1_SW1") (pintype "passive"))
    )
    (net (code "80") (name "SS-XBEE") (class "Default")
      (node (ref "C1") (pin "2") (pinfunction "P$2_2") (pintype "passive"))
      (node (ref "R1") (pin "2") (pinfunction "2_2") (pintype "passive"))
      (node (ref "U$1") (pin "P$1") (pinfunction "PA3_P$1") (pintype "bidirectional"))
    )
    (net (code "81") (name "TX-XBEE") (class "Default")
      (node (ref "U$1") (pin "P$75") (pinfunction "PA0_P$75") (pintype "bidirectional"))
      (node (ref "U$32") (pin "P$18") (pinfunction "RX_P$18") (pintype "bidirectional"))
      (node (ref "X5") (pin "13") (pinfunction "S_13") (pintype "passive"))
      (node (ref "XB1") (pin "3") (pinfunction "DIN/~{CONFIG}_3") (pintype "input"))
    )
    (net (code "82") (name "USART1_RX") (class "Default")
      (node (ref "U$1") (pin "P$57") (pinfunction "PB7_P$57") (pintype "bidirectional"))
    )
    (net (code "83") (name "USART1_TX") (class "Default")
      (node (ref "U$1") (pin "P$56") (pinfunction "PB6_P$56") (pintype "bidirectional"))
    )
    (net (code "84") (name "V-SENSE") (class "Default")
      (node (ref "Q1") (pin "2") (pinfunction "E_2") (pintype "passive"))
      (node (ref "U$1") (pin "P$11") (pinfunction "PE8_P$11") (pintype "bidirectional"))
    )
    (net (code "85") (name "VCC") (class "Default")
      (node (ref "PTC1") (pin "P$2") (pinfunction "2_P$2") (pintype "passive"))
      (node (ref "U$18") (pin "26") (pinfunction "P$7_26") (pintype "bidirectional"))
    )
    (net (code "86") (name "WP") (class "Default")
      (node (ref "U$1") (pin "P$49") (pinfunction "PD3_P$49") (pintype "bidirectional"))
      (node (ref "U$26") (pin "5") (pinfunction "WP_5") (pintype "bidirectional"))
      (node (ref "U$27") (pin "5") (pinfunction "WP_5") (pintype "bidirectional"))
      (node (ref "U$33") (pin "5") (pinfunction "WP_5") (pintype "bidirectional"))
      (node (ref "U$34") (pin "5") (pinfunction "WP_5") (pintype "bidirectional"))
    )
    (net (code "87") (name "unconnected-(J1-VPP-PadC6)") (class "Default")
      (node (ref "J1") (pin "C6") (pinfunction "VPP_C6") (pintype "input"))
    )
    (net (code "88") (name "unconnected-(U$1A-PA4-PadP$2)") (class "Default")
      (node (ref "U$1") (pin "P$2") (pinfunction "PA4_P$2") (pintype "bidirectional"))
    )
    (net (code "89") (name "unconnected-(U$1A-PB0-PadP$8)") (class "Default")
      (node (ref "U$1") (pin "P$8") (pinfunction "PB0_P$8") (pintype "bidirectional"))
    )
    (net (code "90") (name "unconnected-(U$1A-PB1-PadP$9)") (class "Default")
      (node (ref "U$1") (pin "P$9") (pinfunction "PB1_P$9") (pintype "bidirectional"))
    )
    (net (code "91") (name "unconnected-(U$1A-PC4-PadP$6)") (class "Default")
      (node (ref "U$1") (pin "P$6") (pinfunction "PC4_P$6") (pintype "bidirectional"))
    )
    (net (code "92") (name "unconnected-(U$1A-PC5-PadP$7)") (class "Default")
      (node (ref "U$1") (pin "P$7") (pinfunction "PC5_P$7") (pintype "bidirectional"))
    )
    (net (code "93") (name "unconnected-(U$1A-PE7-PadP$10)") (class "Default")
      (node (ref "U$1") (pin "P$10") (pinfunction "PE7_P$10") (pintype "bidirectional"))
    )
    (net (code "94") (name "unconnected-(U$1A-PE9-PadP$12)") (class "Default")
      (node (ref "U$1") (pin "P$12") (pinfunction "PE9_P$12") (pintype "bidirectional"))
    )
    (net (code "95") (name "unconnected-(U$1A-PE10-PadP$13)") (class "Default")
      (node (ref "U$1") (pin "P$13") (pinfunction "PE10_P$13") (pintype "bidirectional"))
    )
    (net (code "96") (name "unconnected-(U$1A-PE11-PadP$14)") (class "Default")
      (node (ref "U$1") (pin "P$14") (pinfunction "PE11_P$14") (pintype "bidirectional"))
    )
    (net (code "97") (name "unconnected-(U$1A-PE12-PadP$15)") (class "Default")
      (node (ref "U$1") (pin "P$15") (pinfunction "PE12_P$15") (pintype "bidirectional"))
    )
    (net (code "98") (name "unconnected-(U$1A-PE13-PadP$16)") (class "Default")
      (node (ref "U$1") (pin "P$16") (pinfunction "PE13_P$16") (pintype "bidirectional"))
    )
    (net (code "99") (name "unconnected-(U$1A-PE14-PadP$17)") (class "Default")
      (node (ref "U$1") (pin "P$17") (pinfunction "PE14_P$17") (pintype "bidirectional"))
    )
    (net (code "100") (name "unconnected-(U$1A-PE15-PadP$18)") (class "Default")
      (node (ref "U$1") (pin "P$18") (pinfunction "PE15_P$18") (pintype "bidirectional"))
    )
    (net (code "101") (name "unconnected-(U$1B-PA9-PadP$40)") (class "Default")
      (node (ref "U$1") (pin "P$40") (pinfunction "PA9_P$40") (pintype "bidirectional"))
    )
    (net (code "102") (name "unconnected-(U$1B-PB14-PadP$25)") (class "Default")
      (node (ref "U$1") (pin "P$25") (pinfunction "PB14_P$25") (pintype "bidirectional"))
    )
    (net (code "103") (name "unconnected-(U$1B-PB15-PadP$26)") (class "Default")
      (node (ref "U$1") (pin "P$26") (pinfunction "PB15_P$26") (pintype "bidirectional"))
    )
    (net (code "104") (name "unconnected-(U$1B-PD8-PadP$27)") (class "Default")
      (node (ref "U$1") (pin "P$27") (pinfunction "PD8_P$27") (pintype "bidirectional"))
    )
    (net (code "105") (name "unconnected-(U$1B-PD9-PadP$28)") (class "Default")
      (node (ref "U$1") (pin "P$28") (pinfunction "PD9_P$28") (pintype "bidirectional"))
    )
    (net (code "106") (name "unconnected-(U$1B-PD10-PadP$29)") (class "Default")
      (node (ref "U$1") (pin "P$29") (pinfunction "PD10_P$29") (pintype "bidirectional"))
    )
    (net (code "107") (name "unconnected-(U$1B-PD11-PadP$30)") (class "Default")
      (node (ref "U$1") (pin "P$30") (pinfunction "PD11_P$30") (pintype "bidirectional"))
    )
    (net (code "108") (name "unconnected-(U$1B-PD12-PadP$31)") (class "Default")
      (node (ref "U$1") (pin "P$31") (pinfunction "PD12_P$31") (pintype "bidirectional"))
    )
    (net (code "109") (name "unconnected-(U$1B-PD13-PadP$32)") (class "Default")
      (node (ref "U$1") (pin "P$32") (pinfunction "PD13_P$32") (pintype "bidirectional"))
    )
    (net (code "110") (name "unconnected-(U$1B-PD14-PadP$33)") (class "Default")
      (node (ref "U$1") (pin "P$33") (pinfunction "PD14_P$33") (pintype "bidirectional"))
    )
    (net (code "111") (name "unconnected-(U$1B-PD15-PadP$34)") (class "Default")
      (node (ref "U$1") (pin "P$34") (pinfunction "PD15_P$34") (pintype "bidirectional"))
    )
    (net (code "112") (name "unconnected-(U$1C-PB5-PadP$55)") (class "Default")
      (node (ref "U$1") (pin "P$55") (pinfunction "PB5_P$55") (pintype "bidirectional"))
    )
    (net (code "113") (name "unconnected-(U$1C-PB8-PadP$58)") (class "Default")
      (node (ref "U$1") (pin "P$58") (pinfunction "PB8_P$58") (pintype "bidirectional"))
    )
    (net (code "114") (name "unconnected-(U$1C-PB9-PadP$59)") (class "Default")
      (node (ref "U$1") (pin "P$59") (pinfunction "PB9_P$59") (pintype "bidirectional"))
    )
    (net (code "115") (name "unconnected-(U$1C-PE0-PadP$60)") (class "Default")
      (node (ref "U$1") (pin "P$60") (pinfunction "PE0_P$60") (pintype "bidirectional"))
    )
    (net (code "116") (name "unconnected-(U$1C-PE1-PadP$61)") (class "Default")
      (node (ref "U$1") (pin "P$61") (pinfunction "PE1_P$61") (pintype "bidirectional"))
    )
    (net (code "117") (name "unconnected-(U$1D-PC0-PadP$71)") (class "Default")
      (node (ref "U$1") (pin "P$71") (pinfunction "PC0_P$71") (pintype "bidirectional"))
    )
    (net (code "118") (name "unconnected-(U$1D-PC1-PadP$72)") (class "Default")
      (node (ref "U$1") (pin "P$72") (pinfunction "PC1_P$72") (pintype "bidirectional"))
    )
    (net (code "119") (name "unconnected-(U$1D-PC2-PadP$73)") (class "Default")
      (node (ref "U$1") (pin "P$73") (pinfunction "PC2_P$73") (pintype "bidirectional"))
    )
    (net (code "120") (name "unconnected-(U$1D-PC13-PadP$68)") (class "Default")
      (node (ref "U$1") (pin "P$68") (pinfunction "PC13_P$68") (pintype "bidirectional"))
    )
    (net (code "121") (name "unconnected-(U$1D-PE2-PadP$63)") (class "Default")
      (node (ref "U$1") (pin "P$63") (pinfunction "PE2_P$63") (pintype "bidirectional"))
    )
    (net (code "122") (name "unconnected-(U$1D-PE4-PadP$65)") (class "Default")
      (node (ref "U$1") (pin "P$65") (pinfunction "PE4_P$65") (pintype "bidirectional"))
    )
    (net (code "123") (name "unconnected-(U$1D-PE6-PadP$67)") (class "Default")
      (node (ref "U$1") (pin "P$67") (pinfunction "PE6_P$67") (pintype "bidirectional"))
    )
    (net (code "124") (name "unconnected-(U$18A-P$4-Pad4)") (class "Default")
      (node (ref "U$18") (pin "4") (pinfunction "P$4_4") (pintype "bidirectional"))
    )
    (net (code "125") (name "unconnected-(U$18A-P$5-Pad5)") (class "Default")
      (node (ref "U$18") (pin "5") (pinfunction "P$5_5") (pintype "bidirectional"))
    )
    (net (code "126") (name "unconnected-(U$18A-P$6-Pad6)") (class "Default")
      (node (ref "U$18") (pin "6") (pinfunction "P$6_6") (pintype "bidirectional"))
    )
    (net (code "127") (name "unconnected-(U$18A-P$7-Pad7)") (class "Default")
      (node (ref "U$18") (pin "7") (pinfunction "P$7_7") (pintype "bidirectional"))
    )
    (net (code "128") (name "unconnected-(U$18B-P$4-Pad11)") (class "Default")
      (node (ref "U$18") (pin "11") (pinfunction "P$4_11") (pintype "bidirectional"))
    )
    (net (code "129") (name "unconnected-(U$18B-P$5-Pad12)") (class "Default")
      (node (ref "U$18") (pin "12") (pinfunction "P$5_12") (pintype "bidirectional"))
    )
    (net (code "130") (name "unconnected-(U$18B-P$6-Pad13)") (class "Default")
      (node (ref "U$18") (pin "13") (pinfunction "P$6_13") (pintype "bidirectional"))
    )
    (net (code "131") (name "unconnected-(U$18C-P$4-Pad17)") (class "Default")
      (node (ref "U$18") (pin "17") (pinfunction "P$4_17") (pintype "bidirectional"))
    )
    (net (code "132") (name "unconnected-(U$18C-P$5-Pad18)") (class "Default")
      (node (ref "U$18") (pin "18") (pinfunction "P$5_18") (pintype "bidirectional"))
    )
    (net (code "133") (name "unconnected-(U$18C-P$6-Pad19)") (class "Default")
      (node (ref "U$18") (pin "19") (pinfunction "P$6_19") (pintype "bidirectional"))
    )
    (net (code "134") (name "unconnected-(U$18D-P$4-Pad23)") (class "Default")
      (node (ref "U$18") (pin "23") (pinfunction "P$4_23") (pintype "bidirectional"))
    )
    (net (code "135") (name "unconnected-(U$18D-P$5-Pad24)") (class "Default")
      (node (ref "U$18") (pin "24") (pinfunction "P$5_24") (pintype "bidirectional"))
    )
    (net (code "136") (name "unconnected-(U$24-G0{slash}SSPND-Pad16)") (class "Default")
      (node (ref "U$24") (pin "16") (pinfunction "G0/SSPND_16") (pintype "bidirectional"))
    )
    (net (code "137") (name "unconnected-(U$24-GP1{slash}USBCFG-Pad15)") (class "Default")
      (node (ref "U$24") (pin "15") (pinfunction "GP1/USBCFG_15") (pintype "bidirectional"))
    )
    (net (code "138") (name "unconnected-(U$24-GP2-Pad14)") (class "Default")
      (node (ref "U$24") (pin "14") (pinfunction "GP2_14") (pintype "bidirectional"))
    )
    (net (code "139") (name "unconnected-(U$24-GP3-Pad9)") (class "Default")
      (node (ref "U$24") (pin "9") (pinfunction "GP3_9") (pintype "bidirectional"))
    )
    (net (code "140") (name "unconnected-(U$24-GP4-Pad8)") (class "Default")
      (node (ref "U$24") (pin "8") (pinfunction "GP4_8") (pintype "bidirectional"))
    )
    (net (code "141") (name "unconnected-(U$24-GP5-Pad7)") (class "Default")
      (node (ref "U$24") (pin "7") (pinfunction "GP5_7") (pintype "bidirectional"))
    )
    (net (code "142") (name "unconnected-(U$24-~{CTS}-Pad13)") (class "Default")
      (node (ref "U$24") (pin "13") (pinfunction "~{CTS}_13") (pintype "bidirectional"))
    )
    (net (code "143") (name "unconnected-(U$24-~{RTS}-Pad11)") (class "Default")
      (node (ref "U$24") (pin "11") (pinfunction "~{RTS}_11") (pintype "bidirectional"))
    )
    (net (code "144") (name "unconnected-(U$29-G0{slash}SSPND-Pad16)") (class "Default")
      (node (ref "U$29") (pin "16") (pinfunction "G0/SSPND_16") (pintype "bidirectional"))
    )
    (net (code "145") (name "unconnected-(U$29-GP1{slash}USBCFG-Pad15)") (class "Default")
      (node (ref "U$29") (pin "15") (pinfunction "GP1/USBCFG_15") (pintype "bidirectional"))
    )
    (net (code "146") (name "unconnected-(U$29-GP2-Pad14)") (class "Default")
      (node (ref "U$29") (pin "14") (pinfunction "GP2_14") (pintype "bidirectional"))
    )
    (net (code "147") (name "unconnected-(U$29-GP3-Pad9)") (class "Default")
      (node (ref "U$29") (pin "9") (pinfunction "GP3_9") (pintype "bidirectional"))
    )
    (net (code "148") (name "unconnected-(U$29-GP4-Pad8)") (class "Default")
      (node (ref "U$29") (pin "8") (pinfunction "GP4_8") (pintype "bidirectional"))
    )
    (net (code "149") (name "unconnected-(U$29-GP5-Pad7)") (class "Default")
      (node (ref "U$29") (pin "7") (pinfunction "GP5_7") (pintype "bidirectional"))
    )
    (net (code "150") (name "unconnected-(U$29-~{CTS}-Pad13)") (class "Default")
      (node (ref "U$29") (pin "13") (pinfunction "~{CTS}_13") (pintype "bidirectional"))
    )
    (net (code "151") (name "unconnected-(U$29-~{RTS}-Pad11)") (class "Default")
      (node (ref "U$29") (pin "11") (pinfunction "~{RTS}_11") (pintype "bidirectional"))
    )
    (net (code "152") (name "unconnected-(U$32-LRNLED-PadP$6)") (class "Default")
      (node (ref "U$32") (pin "P$6") (pinfunction "LRNLED_P$6") (pintype "bidirectional"))
    )
    (net (code "153") (name "unconnected-(U$32-LRNSW-PadP$5)") (class "Default")
      (node (ref "U$32") (pin "P$5") (pinfunction "LRNSW_P$5") (pintype "bidirectional"))
    )
    (net (code "154") (name "unconnected-(U$32-OP1-PadP$3)") (class "Default")
      (node (ref "U$32") (pin "P$3") (pinfunction "OP1_P$3") (pintype "bidirectional"))
    )
    (net (code "155") (name "unconnected-(U$32-OP2-PadP$4)") (class "Default")
      (node (ref "U$32") (pin "P$4") (pinfunction "OP2_P$4") (pintype "bidirectional"))
    )
    (net (code "156") (name "unconnected-(U$32-OP3-PadP$7)") (class "Default")
      (node (ref "U$32") (pin "P$7") (pinfunction "OP3_P$7") (pintype "bidirectional"))
    )
    (net (code "157") (name "unconnected-(U$32-OP4-PadP$8)") (class "Default")
      (node (ref "U$32") (pin "P$8") (pinfunction "OP4_P$8") (pintype "bidirectional"))
    )
    (net (code "158") (name "unconnected-(U$32-OP5-PadP$9)") (class "Default")
      (node (ref "U$32") (pin "P$9") (pinfunction "OP5_P$9") (pintype "bidirectional"))
    )
    (net (code "159") (name "unconnected-(U$32-OP6-PadP$11)") (class "Default")
      (node (ref "U$32") (pin "P$11") (pinfunction "OP6_P$11") (pintype "bidirectional"))
    )
    (net (code "160") (name "unconnected-(U$32-OP7-PadP$12)") (class "Default")
      (node (ref "U$32") (pin "P$12") (pinfunction "OP7_P$12") (pintype "bidirectional"))
    )
    (net (code "161") (name "unconnected-(U$32-OP8-PadP$13)") (class "Default")
      (node (ref "U$32") (pin "P$13") (pinfunction "OP8_P$13") (pintype "bidirectional"))
    )
    (net (code "162") (name "unconnected-(U$32-OPT1-PadP$10)") (class "Default")
      (node (ref "U$32") (pin "P$10") (pinfunction "OPT1_P$10") (pintype "bidirectional"))
    )
    (net (code "163") (name "unconnected-(U$36-NC-Pad6)") (class "Default")
      (node (ref "U$36") (pin "6") (pinfunction "NC_6") (pintype "bidirectional"))
    )
    (net (code "164") (name "unconnected-(U3-R1IN-Pad13)") (class "Default")
      (node (ref "U3") (pin "13") (pinfunction "R1IN_13") (pintype "input"))
    )
    (net (code "165") (name "unconnected-(U3-R1OUT-Pad12)") (class "Default")
      (node (ref "U3") (pin "12") (pinfunction "R1OUT_12") (pintype "output"))
    )
    (net (code "166") (name "unconnected-(U3-T1IN-Pad11)") (class "Default")
      (node (ref "U3") (pin "11") (pinfunction "T1IN_11") (pintype "input"))
    )
    (net (code "167") (name "unconnected-(U3-T1OUT-Pad14)") (class "Default")
      (node (ref "U3") (pin "14") (pinfunction "T1OUT_14") (pintype "output"))
    )
    (net (code "168") (name "unconnected-(X1-PadSW2)") (class "Default")
      (node (ref "X1") (pin "SW2") (pinfunction "SW2_SW2") (pintype "passive"))
    )
    (net (code "169") (name "unconnected-(X5A-S-Pad1)") (class "Default")
      (node (ref "X5") (pin "1") (pinfunction "S_1") (pintype "passive"))
    )
    (net (code "170") (name "unconnected-(X5AA-S-Pad33)") (class "Default")
      (node (ref "X5") (pin "33") (pinfunction "S_33") (pintype "passive"))
    )
    (net (code "171") (name "unconnected-(X5AD-S-Pad36)") (class "Default")
      (node (ref "X5") (pin "36") (pinfunction "S_36") (pintype "passive"))
    )
    (net (code "172") (name "unconnected-(X5AF-S-Pad38)") (class "Default")
      (node (ref "X5") (pin "38") (pinfunction "S_38") (pintype "passive"))
    )
    (net (code "173") (name "unconnected-(X5AK-S-Pad42)") (class "Default")
      (node (ref "X5") (pin "42") (pinfunction "S_42") (pintype "passive"))
    )
    (net (code "174") (name "unconnected-(X5AM-S-Pad44)") (class "Default")
      (node (ref "X5") (pin "44") (pinfunction "S_44") (pintype "passive"))
    )
    (net (code "175") (name "unconnected-(X5AN-S-Pad45)") (class "Default")
      (node (ref "X5") (pin "45") (pinfunction "S_45") (pintype "passive"))
    )
    (net (code "176") (name "unconnected-(X5AO-S-Pad46)") (class "Default")
      (node (ref "X5") (pin "46") (pinfunction "S_46") (pintype "passive"))
    )
    (net (code "177") (name "unconnected-(X5AP-S-Pad47)") (class "Default")
      (node (ref "X5") (pin "47") (pinfunction "S_47") (pintype "passive"))
    )
    (net (code "178") (name "unconnected-(X5AQ-S-Pad48)") (class "Default")
      (node (ref "X5") (pin "48") (pinfunction "S_48") (pintype "passive"))
    )
    (net (code "179") (name "unconnected-(X5AR-S-Pad49)") (class "Default")
      (node (ref "X5") (pin "49") (pinfunction "S_49") (pintype "passive"))
    )
    (net (code "180") (name "unconnected-(X5AS-S-Pad5)") (class "Default")
      (node (ref "X5") (pin "5") (pinfunction "S_5") (pintype "passive"))
    )
    (net (code "181") (name "unconnected-(X5AU-S-Pad51)") (class "Default")
      (node (ref "X5") (pin "51") (pinfunction "S_51") (pintype "passive"))
    )
    (net (code "182") (name "unconnected-(X5AW-S-Pad6)") (class "Default")
      (node (ref "X5") (pin "6") (pinfunction "S_6") (pintype "passive"))
    )
    (net (code "183") (name "unconnected-(X5AX-S-Pad7)") (class "Default")
      (node (ref "X5") (pin "7") (pinfunction "S_7") (pintype "passive"))
    )
    (net (code "184") (name "unconnected-(X5H-S-Pad16)") (class "Default")
      (node (ref "X5") (pin "16") (pinfunction "S_16") (pintype "passive"))
    )
    (net (code "185") (name "unconnected-(X5I-S-Pad17)") (class "Default")
      (node (ref "X5") (pin "17") (pinfunction "S_17") (pintype "passive"))
    )
    (net (code "186") (name "unconnected-(X5K-S-Pad19)") (class "Default")
      (node (ref "X5") (pin "19") (pinfunction "S_19") (pintype "passive"))
    )
    (net (code "187") (name "unconnected-(X5M-S-Pad20)") (class "Default")
      (node (ref "X5") (pin "20") (pinfunction "S_20") (pintype "passive"))
    )
    (net (code "188") (name "unconnected-(X5O-S-Pad22)") (class "Default")
      (node (ref "X5") (pin "22") (pinfunction "S_22") (pintype "passive"))
    )
    (net (code "189") (name "unconnected-(X5P-S-Pad23)") (class "Default")
      (node (ref "X5") (pin "23") (pinfunction "S_23") (pintype "passive"))
    )
    (net (code "190") (name "unconnected-(X5Q-S-Pad24)") (class "Default")
      (node (ref "X5") (pin "24") (pinfunction "S_24") (pintype "passive"))
    )
    (net (code "191") (name "unconnected-(X5R-S-Pad25)") (class "Default")
      (node (ref "X5") (pin "25") (pinfunction "S_25") (pintype "passive"))
    )
    (net (code "192") (name "unconnected-(X5U-S-Pad28)") (class "Default")
      (node (ref "X5") (pin "28") (pinfunction "S_28") (pintype "passive"))
    )
    (net (code "193") (name "unconnected-(X5W-S-Pad3)") (class "Default")
      (node (ref "X5") (pin "3") (pinfunction "S_3") (pintype "passive"))
    )
    (net (code "194") (name "unconnected-(X5X-S-Pad30)") (class "Default")
      (node (ref "X5") (pin "30") (pinfunction "S_30") (pintype "passive"))
    )
    (net (code "195") (name "unconnected-(X5Y-S-Pad31)") (class "Default")
      (node (ref "X5") (pin "31") (pinfunction "S_31") (pintype "passive"))
    )
    (net (code "196") (name "unconnected-(X5Z-S-Pad32)") (class "Default")
      (node (ref "X5") (pin "32") (pinfunction "S_32") (pintype "passive"))
    )
    (net (code "197") (name "unconnected-(XB1-AD0{slash}DIO0-Pad20)") (class "Default")
      (node (ref "XB1") (pin "20") (pinfunction "AD0/DIO0_20") (pintype "bidirectional"))
    )
    (net (code "198") (name "unconnected-(XB1-AD1{slash}DIO1-Pad19)") (class "Default")
      (node (ref "XB1") (pin "19") (pinfunction "AD1/DIO1_19") (pintype "bidirectional"))
    )
    (net (code "199") (name "unconnected-(XB1-AD2{slash}DIO2-Pad18)") (class "Default")
      (node (ref "XB1") (pin "18") (pinfunction "AD2/DIO2_18") (pintype "bidirectional"))
    )
    (net (code "200") (name "unconnected-(XB1-CD{slash}DOUT_EN{slash}DO8-Pad4)") (class "Default")
      (node (ref "XB1") (pin "4") (pinfunction "CD/DOUT_EN/DO8_4") (pintype "output"))
    )
    (net (code "201") (name "unconnected-(XB1-COORD_SEL{slash}AD3{slash}DIO3-Pad17)") (class "Default")
      (node (ref "XB1") (pin "17") (pinfunction "COORD_SEL/AD3/DIO3_17") (pintype "bidirectional"))
    )
    (net (code "202") (name "unconnected-(XB1-ON{slash}~{SLEEP}-Pad13)") (class "Default")
      (node (ref "XB1") (pin "13") (pinfunction "ON/~{SLEEP}_13") (pintype "output"))
    )
    (net (code "203") (name "unconnected-(XB1-RF_TX{slash}AD4{slash}DIO4-Pad11)") (class "Default")
      (node (ref "XB1") (pin "11") (pinfunction "RF_TX/AD4/DIO4_11") (pintype "bidirectional"))
    )
    (net (code "204") (name "unconnected-(XB1-VREF-Pad14)") (class "Default")
      (node (ref "XB1") (pin "14") (pinfunction "VREF_14") (pintype "input"))
    )
    (net (code "205") (name "unconnected-(XB1-~{DTR}{slash}SLEEP_RQ{slash}DI8-Pad9)") (class "Default")
      (node (ref "XB1") (pin "9") (pinfunction "~{DTR}/SLEEP_RQ/DI8_9") (pintype "bidirectional"))
    )
  )
)
